# Test_Schematic_V3.net
KiCad netlist of a schematic drawn in EAGLE
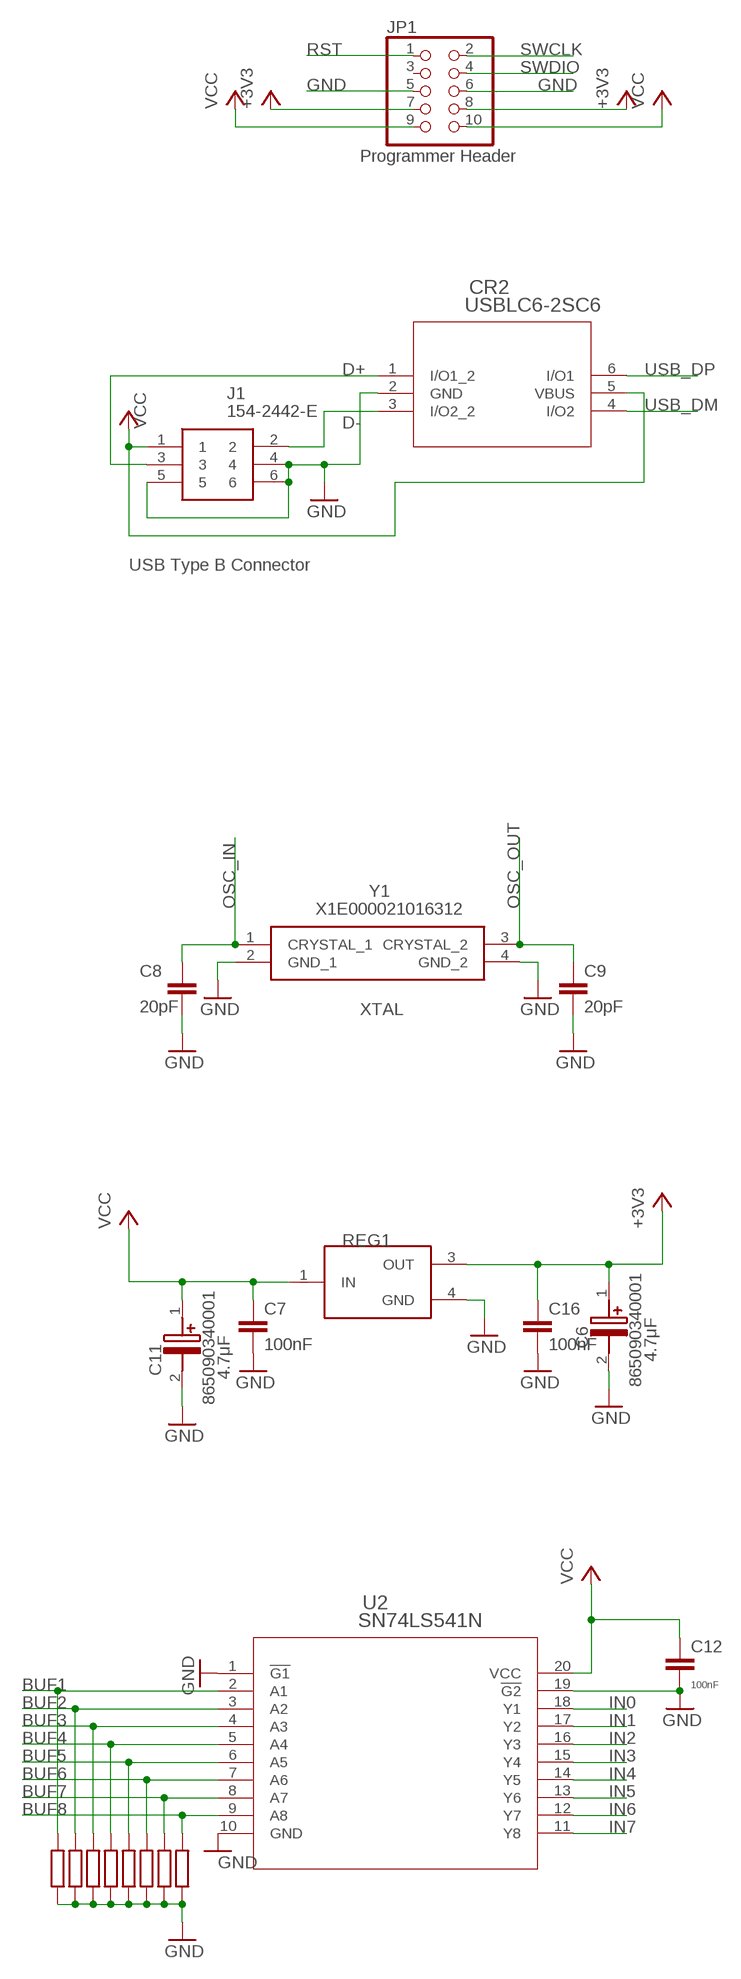
[diagram p0: schematic, sheet 1, part 1 of 2]
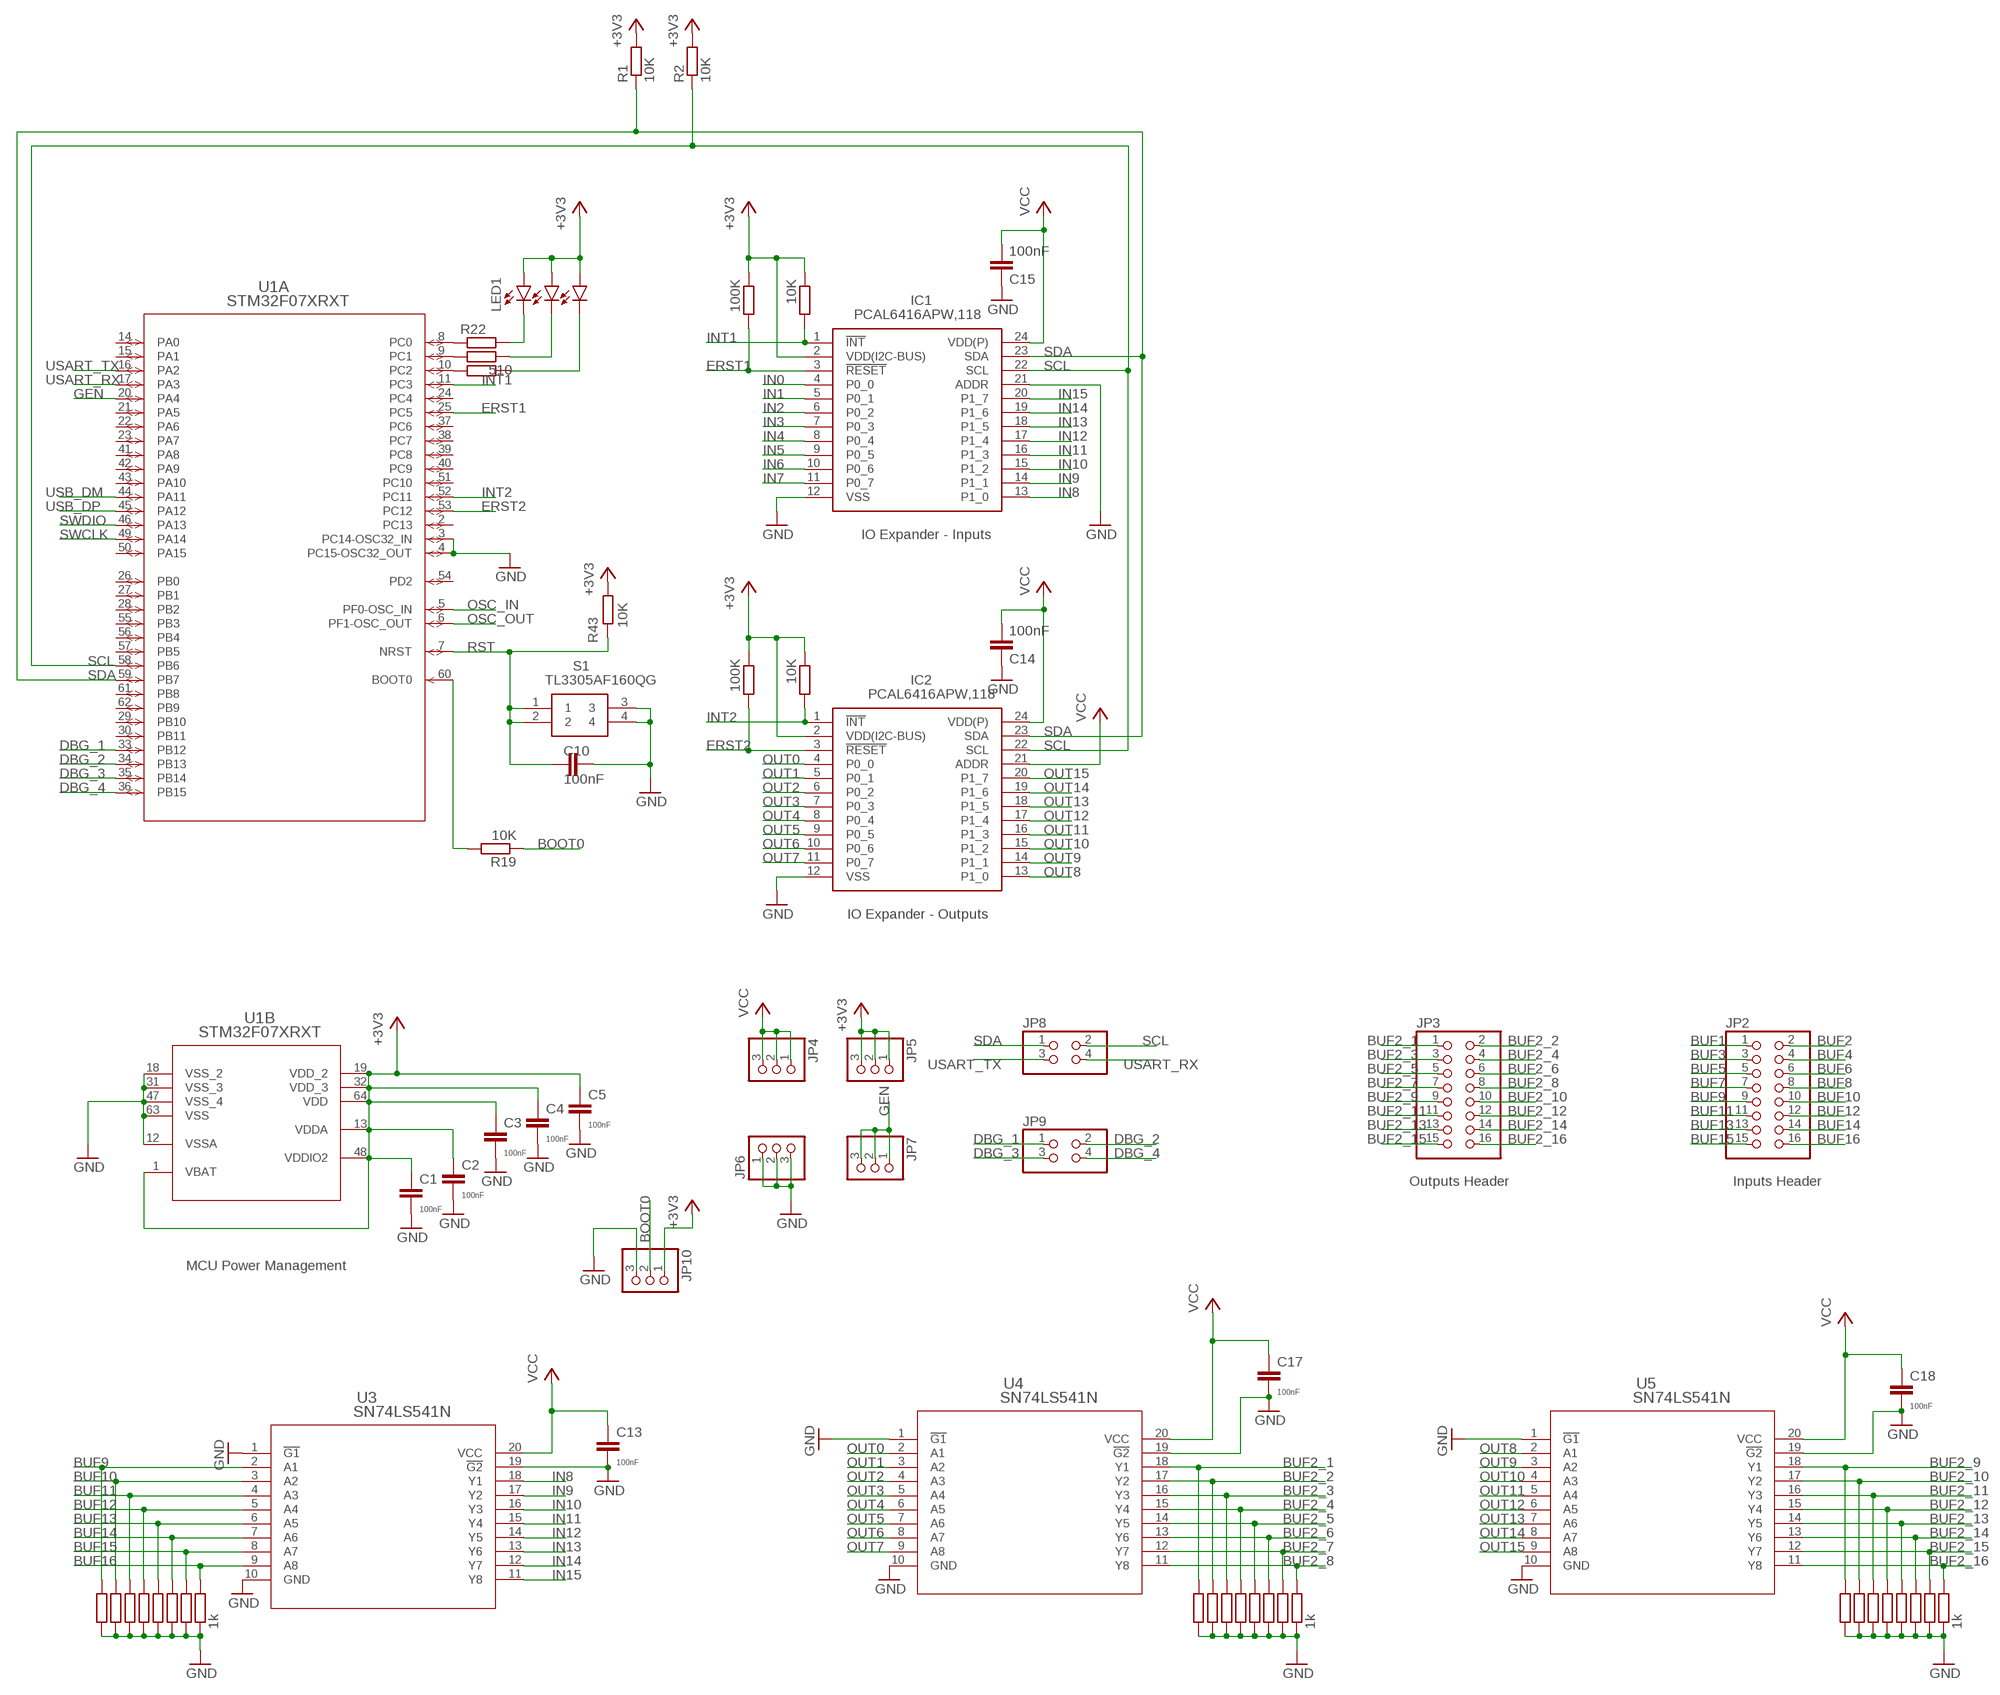
[diagram p1: schematic, sheet 1, part 2 of 2]

(export (version "E")
  (design (tool "Eeschema 10.0.6"))
  (components
    (comp (ref "C1")
      (value "100nF")
      (footprint "eagle-import:C1206")
      (libsource (lib "eagle-import") (part "C-EUC1206"))
    )
    (comp (ref "C2")
      (value "100nF")
      (footprint "eagle-import:C1206")
      (libsource (lib "eagle-import") (part "C-EUC1206"))
    )
    (comp (ref "C3")
      (value "100nF")
      (footprint "eagle-import:C1206")
      (libsource (lib "eagle-import") (part "C-EUC1206"))
    )
    (comp (ref "C4")
      (value "100nF")
      (footprint "eagle-import:C1206")
      (libsource (lib "eagle-import") (part "C-EUC1206"))
    )
    (comp (ref "C5")
      (value "100nF")
      (footprint "eagle-import:C1206")
      (libsource (lib "eagle-import") (part "C-EUC1206"))
    )
    (comp (ref "C6")
      (value "865090340001")
      (footprint "eagle-import:CAPAE430X550N")
      (fields
        (field (name "MOUSER_PART_NUMBER") "710-865090340001")
        (field (name "RS_PART_NUMBER") "8387942P")
        (field (name "CAPACITANCE") "4.7μF")
      )
      (libsource (lib "eagle-import") (part "865090340001"))
    )
    (comp (ref "C7")
      (value "100nF")
      (footprint "eagle-import:C1206")
      (libsource (lib "eagle-import") (part "C-EUC1206"))
    )
    (comp (ref "C8")
      (value "20pF")
      (footprint "eagle-import:C0805K")
      (libsource (lib "eagle-import") (part "C-EUC0805K"))
    )
    (comp (ref "C9")
      (value "20pF")
      (footprint "eagle-import:C0805K")
      (libsource (lib "eagle-import") (part "C-EUC0805K"))
    )
    (comp (ref "C10")
      (value "100nF")
      (footprint "eagle-import:C1206")
      (libsource (lib "eagle-import") (part "C-EUC1206"))
    )
    (comp (ref "C11")
      (value "865090340001")
      (footprint "eagle-import:CAPAE430X550N")
      (fields
        (field (name "MOUSER_PART_NUMBER") "710-865090340001")
        (field (name "RS_PART_NUMBER") "8387942P")
        (field (name "CAPACITANCE") "4.7μF")
      )
      (libsource (lib "eagle-import") (part "865090340001"))
    )
    (comp (ref "C12")
      (value "100nF")
      (footprint "eagle-import:C1206")
      (libsource (lib "eagle-import") (part "C-EUC1206"))
    )
    (comp (ref "C13")
      (value "100nF")
      (footprint "eagle-import:C1206")
      (libsource (lib "eagle-import") (part "C-EUC1206"))
    )
    (comp (ref "C14")
      (value "100nF")
      (footprint "eagle-import:C1206")
      (libsource (lib "eagle-import") (part "C-EUC1206"))
    )
    (comp (ref "C15")
      (value "100nF")
      (footprint "eagle-import:C1206")
      (libsource (lib "eagle-import") (part "C-EUC1206"))
    )
    (comp (ref "C16")
      (value "100nF")
      (footprint "eagle-import:C1206")
      (libsource (lib "eagle-import") (part "C-EUC1206"))
    )
    (comp (ref "C17")
      (value "100nF")
      (footprint "eagle-import:C1206")
      (libsource (lib "eagle-import") (part "C-EUC1206"))
    )
    (comp (ref "C18")
      (value "100nF")
      (footprint "eagle-import:C1206")
      (libsource (lib "eagle-import") (part "C-EUC1206"))
    )
    (comp (ref "CR2")
      (value "USBLC6-2SC6")
      (footprint "eagle-import:SOT23-6L")
      (fields (field (name "MANUFACTURER_PART_NUMBER") "USBLC62SC6"))
      (libsource (lib "eagle-import") (part "USBLC6-2SC6"))
    )
    (comp (ref "IC1")
      (value "PCAL6416APW,118")
      (footprint "eagle-import:SOP65P640X110-24N")
      (fields
        (field (name "MOUSER_PART_NUMBER") "771-PCAL6416APW118")
        (field (name "CUSTOM_DESCRIPTION") "IO Expander - Inputs")
      )
      (libsource (lib "eagle-import") (part "PCAL6416APW,118"))
    )
    (comp (ref "IC2")
      (value "PCAL6416APW,118")
      (footprint "eagle-import:SOP65P640X110-24N")
      (fields
        (field (name "MOUSER_PART_NUMBER") "771-PCAL6416APW118")
        (field (name "CUSTOM_DESCRIPTION") "IO Expander - Outputs")
      )
      (libsource (lib "eagle-import") (part "PCAL6416APW,118"))
    )
    (comp (ref "J1")
      (value "154-2442-E")
      (footprint "eagle-import:1542442E")
      (fields (field (name "CUSTOM_DESCRIPTION") "USB Type B Connector"))
      (libsource (lib "eagle-import") (part "154-2442-E"))
    )
    (comp (ref "JP1")
      (value "PINHD-2X5")
      (footprint "eagle-import:2X05")
      (fields (field (name "HEADER") "Programmer Header"))
      (libsource (lib "eagle-import") (part "PINHD-2X5"))
    )
    (comp (ref "JP2")
      (value "PINHD-2X8")
      (footprint "eagle-import:2X08")
      (fields (field (name "CUSTOM_DESCRIPTION") "Inputs Header"))
      (libsource (lib "eagle-import") (part "PINHD-2X8"))
    )
    (comp (ref "JP3")
      (value "PINHD-2X8")
      (footprint "eagle-import:2X08")
      (fields (field (name "CUSTOM_DESCRIPTION") "Outputs Header"))
      (libsource (lib "eagle-import") (part "PINHD-2X8"))
    )
    (comp (ref "JP4")
      (value "PINHD-1X3")
      (footprint "eagle-import:1X03")
      (libsource (lib "eagle-import") (part "PINHD-1X3"))
    )
    (comp (ref "JP5")
      (value "PINHD-1X3")
      (footprint "eagle-import:1X03")
      (libsource (lib "eagle-import") (part "PINHD-1X3"))
    )
    (comp (ref "JP6")
      (value "PINHD-1X3")
      (footprint "eagle-import:1X03")
      (libsource (lib "eagle-import") (part "PINHD-1X3"))
    )
    (comp (ref "JP7")
      (value "PINHD-1X3")
      (footprint "eagle-import:1X03")
      (libsource (lib "eagle-import") (part "PINHD-1X3"))
    )
    (comp (ref "JP8")
      (value "PINHD-2X2")
      (footprint "eagle-import:2X02")
      (libsource (lib "eagle-import") (part "PINHD-2X2"))
    )
    (comp (ref "JP9")
      (value "PINHD-2X2")
      (footprint "eagle-import:2X02")
      (libsource (lib "eagle-import") (part "PINHD-2X2"))
    )
    (comp (ref "JP10")
      (value "PINHD-1X3")
      (footprint "eagle-import:1X03")
      (libsource (lib "eagle-import") (part "PINHD-1X3"))
    )
    (comp (ref "LED1")
      (value "LEDCHIP-LED0805")
      (footprint "eagle-import:CHIP-LED0805")
      (libsource (lib "eagle-import") (part "LEDCHIP-LED0805"))
    )
    (comp (ref "LED2")
      (value "LEDCHIP-LED0805")
      (footprint "eagle-import:CHIP-LED0805")
      (libsource (lib "eagle-import") (part "LEDCHIP-LED0805"))
    )
    (comp (ref "LED3")
      (value "LEDCHIP-LED0805")
      (footprint "eagle-import:CHIP-LED0805")
      (libsource (lib "eagle-import") (part "LEDCHIP-LED0805"))
    )
    (comp (ref "R1")
      (value "10K")
      (footprint "eagle-import:R2010")
      (libsource (lib "eagle-import") (part "R-EU_R2010"))
    )
    (comp (ref "R2")
      (value "10K")
      (footprint "eagle-import:R2010")
      (libsource (lib "eagle-import") (part "R-EU_R2010"))
    )
    (comp (ref "R11")
      (value "R-EU_R0805")
      (footprint "eagle-import:R0805")
      (libsource (lib "eagle-import") (part "R-EU_R0805"))
    )
    (comp (ref "R12")
      (value "R-EU_R0805")
      (footprint "eagle-import:R0805")
      (libsource (lib "eagle-import") (part "R-EU_R0805"))
    )
    (comp (ref "R13")
      (value "R-EU_R0805")
      (footprint "eagle-import:R0805")
      (libsource (lib "eagle-import") (part "R-EU_R0805"))
    )
    (comp (ref "R14")
      (value "R-EU_R0805")
      (footprint "eagle-import:R0805")
      (libsource (lib "eagle-import") (part "R-EU_R0805"))
    )
    (comp (ref "R15")
      (value "R-EU_R0805")
      (footprint "eagle-import:R0805")
      (libsource (lib "eagle-import") (part "R-EU_R0805"))
    )
    (comp (ref "R16")
      (value "R-EU_R0805")
      (footprint "eagle-import:R0805")
      (libsource (lib "eagle-import") (part "R-EU_R0805"))
    )
    (comp (ref "R17")
      (value "R-EU_R0805")
      (footprint "eagle-import:R0805")
      (libsource (lib "eagle-import") (part "R-EU_R0805"))
    )
    (comp (ref "R18")
      (value "1k")
      (footprint "eagle-import:R0805")
      (libsource (lib "eagle-import") (part "R-EU_R0805"))
    )
    (comp (ref "R19")
      (value "10K")
      (footprint "eagle-import:R2010")
      (libsource (lib "eagle-import") (part "R-EU_R2010"))
    )
    (comp (ref "R20")
      (value "100K")
      (footprint "eagle-import:R2010")
      (libsource (lib "eagle-import") (part "R-EU_R2010"))
    )
    (comp (ref "R21")
      (value "100K")
      (footprint "eagle-import:R2010")
      (libsource (lib "eagle-import") (part "R-EU_R2010"))
    )
    (comp (ref "R22")
      (value "R-EU_R0805")
      (footprint "eagle-import:R0805")
      (libsource (lib "eagle-import") (part "R-EU_R0805"))
    )
    (comp (ref "R23")
      (value "R-EU_R0805")
      (footprint "eagle-import:R0805")
      (libsource (lib "eagle-import") (part "R-EU_R0805"))
    )
    (comp (ref "R24")
      (value "510")
      (footprint "eagle-import:R0805")
      (libsource (lib "eagle-import") (part "R-EU_R0805"))
    )
    (comp (ref "R25")
      (value "10K")
      (footprint "eagle-import:R2010")
      (libsource (lib "eagle-import") (part "R-EU_R2010"))
    )
    (comp (ref "R26")
      (value "10K")
      (footprint "eagle-import:R2010")
      (libsource (lib "eagle-import") (part "R-EU_R2010"))
    )
    (comp (ref "R27")
      (value "1k")
      (footprint "eagle-import:R0805")
      (libsource (lib "eagle-import") (part "R-EU_R0805"))
    )
    (comp (ref "R28")
      (value "R-EU_R0805")
      (footprint "eagle-import:R0805")
      (libsource (lib "eagle-import") (part "R-EU_R0805"))
    )
    (comp (ref "R29")
      (value "R-EU_R0805")
      (footprint "eagle-import:R0805")
      (libsource (lib "eagle-import") (part "R-EU_R0805"))
    )
    (comp (ref "R30")
      (value "R-EU_R0805")
      (footprint "eagle-import:R0805")
      (libsource (lib "eagle-import") (part "R-EU_R0805"))
    )
    (comp (ref "R31")
      (value "R-EU_R0805")
      (footprint "eagle-import:R0805")
      (libsource (lib "eagle-import") (part "R-EU_R0805"))
    )
    (comp (ref "R32")
      (value "R-EU_R0805")
      (footprint "eagle-import:R0805")
      (libsource (lib "eagle-import") (part "R-EU_R0805"))
    )
    (comp (ref "R33")
      (value "R-EU_R0805")
      (footprint "eagle-import:R0805")
      (libsource (lib "eagle-import") (part "R-EU_R0805"))
    )
    (comp (ref "R34")
      (value "R-EU_R0805")
      (footprint "eagle-import:R0805")
      (libsource (lib "eagle-import") (part "R-EU_R0805"))
    )
    (comp (ref "R43")
      (value "10K")
      (footprint "eagle-import:R0805")
      (libsource (lib "eagle-import") (part "R-EU_R0805"))
    )
    (comp (ref "R44")
      (value "1k")
      (footprint "eagle-import:R0805")
      (libsource (lib "eagle-import") (part "R-EU_R0805"))
    )
    (comp (ref "R45")
      (value "R-EU_R0805")
      (footprint "eagle-import:R0805")
      (libsource (lib "eagle-import") (part "R-EU_R0805"))
    )
    (comp (ref "R46")
      (value "R-EU_R0805")
      (footprint "eagle-import:R0805")
      (libsource (lib "eagle-import") (part "R-EU_R0805"))
    )
    (comp (ref "R47")
      (value "R-EU_R0805")
      (footprint "eagle-import:R0805")
      (libsource (lib "eagle-import") (part "R-EU_R0805"))
    )
    (comp (ref "R48")
      (value "R-EU_R0805")
      (footprint "eagle-import:R0805")
      (libsource (lib "eagle-import") (part "R-EU_R0805"))
    )
    (comp (ref "R49")
      (value "R-EU_R0805")
      (footprint "eagle-import:R0805")
      (libsource (lib "eagle-import") (part "R-EU_R0805"))
    )
    (comp (ref "R50")
      (value "R-EU_R0805")
      (footprint "eagle-import:R0805")
      (libsource (lib "eagle-import") (part "R-EU_R0805"))
    )
    (comp (ref "R51")
      (value "R-EU_R0805")
      (footprint "eagle-import:R0805")
      (libsource (lib "eagle-import") (part "R-EU_R0805"))
    )
    (comp (ref "R52")
      (value "1k")
      (footprint "eagle-import:R0805")
      (libsource (lib "eagle-import") (part "R-EU_R0805"))
    )
    (comp (ref "R53")
      (value "R-EU_R0805")
      (footprint "eagle-import:R0805")
      (libsource (lib "eagle-import") (part "R-EU_R0805"))
    )
    (comp (ref "R54")
      (value "R-EU_R0805")
      (footprint "eagle-import:R0805")
      (libsource (lib "eagle-import") (part "R-EU_R0805"))
    )
    (comp (ref "R55")
      (value "R-EU_R0805")
      (footprint "eagle-import:R0805")
      (libsource (lib "eagle-import") (part "R-EU_R0805"))
    )
    (comp (ref "R56")
      (value "R-EU_R0805")
      (footprint "eagle-import:R0805")
      (libsource (lib "eagle-import") (part "R-EU_R0805"))
    )
    (comp (ref "R57")
      (value "R-EU_R0805")
      (footprint "eagle-import:R0805")
      (libsource (lib "eagle-import") (part "R-EU_R0805"))
    )
    (comp (ref "R58")
      (value "R-EU_R0805")
      (footprint "eagle-import:R0805")
      (libsource (lib "eagle-import") (part "R-EU_R0805"))
    )
    (comp (ref "R59")
      (value "R-EU_R0805")
      (footprint "eagle-import:R0805")
      (libsource (lib "eagle-import") (part "R-EU_R0805"))
    )
    (comp (ref "REG1")
      (value "LF33ABDT")
      (footprint "eagle-import:DPAK")
      (libsource (lib "eagle-import") (part "LF33ABDT"))
    )
    (comp (ref "S1")
      (value "TL3305AF160QG")
      (footprint "eagle-import:TL3305AF160QG")
      (fields (field (name "MOUSER_PART_NUMBER") "612-TL3305AF160QG"))
      (libsource (lib "eagle-import") (part "TL3305AF160QG"))
    )
    (comp (ref "U1")
      (value "STM32F07XRXT")
      (footprint "eagle-import:LQFP64-10X10MM")
      (fields (field (name "CUSTOM_DESCRIPTION") "MCU Power Management"))
      (libsource (lib "eagle-import") (part "STM32F07XRXT"))
    )
    (comp (ref "U2")
      (value "SN74LS541N")
      (footprint "eagle-import:N20")
      (libsource (lib "eagle-import") (part "SN74LS541N"))
    )
    (comp (ref "U3")
      (value "SN74LS541N")
      (footprint "eagle-import:N20")
      (libsource (lib "eagle-import") (part "SN74LS541N"))
    )
    (comp (ref "U4")
      (value "SN74LS541N")
      (footprint "eagle-import:N20")
      (libsource (lib "eagle-import") (part "SN74LS541N"))
    )
    (comp (ref "U5")
      (value "SN74LS541N")
      (footprint "eagle-import:N20")
      (libsource (lib "eagle-import") (part "SN74LS541N"))
    )
    (comp (ref "Y1")
      (value "X1E000021016312")
      (footprint "eagle-import:TSX-3225_2")
      (fields (field (name "RS_PART_NUMBER") "9047556P") (field (name "CUSTOM_DESCRIPTION") "XTAL"))
      (libsource (lib "eagle-import") (part "X1E000021016312"))
    )
  )
  (nets
    (net (code "1") (name "+3V3") (class "Default")
      (node (ref "C1") (pin "1") (pinfunction "1_1") (pintype "passive"))
      (node (ref "C16") (pin "1") (pinfunction "1_1") (pintype "passive"))
      (node (ref "C2") (pin "1") (pinfunction "1_1") (pintype "passive"))
      (node (ref "C3") (pin "1") (pinfunction "1_1") (pintype "passive"))
      (node (ref "C4") (pin "1") (pinfunction "1_1") (pintype "passive"))
      (node (ref "C5") (pin "1") (pinfunction "1_1") (pintype "passive"))
      (node (ref "C6") (pin "1") (pinfunction "+_1") (pintype "bidirectional"))
      (node (ref "IC1") (pin "2") (pinfunction "VDD(I2C-BUS)_2") (pintype "bidirectional"))
      (node (ref "IC2") (pin "2") (pinfunction "VDD(I2C-BUS)_2") (pintype "bidirectional"))
      (node (ref "JP1") (pin "7") (pinfunction "7_7") (pintype "passive"))
      (node (ref "JP1") (pin "8") (pinfunction "8_8") (pintype "passive"))
      (node (ref "JP10") (pin "1") (pinfunction "1_1") (pintype "passive"))
      (node (ref "JP5") (pin "1") (pinfunction "1_1") (pintype "passive"))
      (node (ref "JP5") (pin "2") (pinfunction "2_2") (pintype "passive"))
      (node (ref "JP5") (pin "3") (pinfunction "3_3") (pintype "passive"))
      (node (ref "LED1") (pin "A") (pinfunction "A_A") (pintype "passive"))
      (node (ref "LED2") (pin "A") (pinfunction "A_A") (pintype "passive"))
      (node (ref "LED3") (pin "A") (pinfunction "A_A") (pintype "passive"))
      (node (ref "R1") (pin "2") (pinfunction "2_2") (pintype "passive"))
      (node (ref "R2") (pin "2") (pinfunction "2_2") (pintype "passive"))
      (node (ref "R20") (pin "1") (pinfunction "1_1") (pintype "passive"))
      (node (ref "R21") (pin "1") (pinfunction "1_1") (pintype "passive"))
      (node (ref "R25") (pin "1") (pinfunction "1_1") (pintype "passive"))
      (node (ref "R26") (pin "1") (pinfunction "1_1") (pintype "passive"))
      (node (ref "R43") (pin "1") (pinfunction "1_1") (pintype "passive"))
      (node (ref "REG1") (pin "3") (pinfunction "OUT_3") (pintype "power_in"))
      (node (ref "U1") (pin "1") (pinfunction "VBAT_1") (pintype "power_in"))
      (node (ref "U1") (pin "13") (pinfunction "VDDA_13") (pintype "power_in"))
      (node (ref "U1") (pin "19") (pinfunction "VDD_2_19") (pintype "power_in"))
      (node (ref "U1") (pin "32") (pinfunction "VDD_3_32") (pintype "power_in"))
      (node (ref "U1") (pin "48") (pinfunction "VDDIO2_48") (pintype "power_in"))
      (node (ref "U1") (pin "64") (pinfunction "VDD_64") (pintype "power_in"))
    )
    (net (code "2") (name "/BOOT0") (class "Default")
      (node (ref "JP10") (pin "2") (pinfunction "2_2") (pintype "passive"))
      (node (ref "R19") (pin "1") (pinfunction "1_1") (pintype "passive"))
    )
    (net (code "3") (name "/BUF1") (class "Default")
      (node (ref "JP2") (pin "1") (pinfunction "1_1") (pintype "passive"))
      (node (ref "R11") (pin "2") (pinfunction "2_2") (pintype "passive"))
      (node (ref "U2") (pin "2") (pinfunction "A1_2") (pintype "input"))
    )
    (net (code "4") (name "/BUF2") (class "Default")
      (node (ref "JP2") (pin "2") (pinfunction "2_2") (pintype "passive"))
      (node (ref "R12") (pin "2") (pinfunction "2_2") (pintype "passive"))
      (node (ref "U2") (pin "3") (pinfunction "A2_3") (pintype "input"))
    )
    (net (code "5") (name "/BUF2_1") (class "Default")
      (node (ref "JP3") (pin "1") (pinfunction "1_1") (pintype "passive"))
      (node (ref "R51") (pin "2") (pinfunction "2_2") (pintype "passive"))
      (node (ref "U4") (pin "18") (pinfunction "Y1_18") (pintype "output"))
    )
    (net (code "6") (name "/BUF2_2") (class "Default")
      (node (ref "JP3") (pin "2") (pinfunction "2_2") (pintype "passive"))
      (node (ref "R50") (pin "2") (pinfunction "2_2") (pintype "passive"))
      (node (ref "U4") (pin "17") (pinfunction "Y2_17") (pintype "output"))
    )
    (net (code "7") (name "/BUF2_3") (class "Default")
      (node (ref "JP3") (pin "3") (pinfunction "3_3") (pintype "passive"))
      (node (ref "R49") (pin "2") (pinfunction "2_2") (pintype "passive"))
      (node (ref "U4") (pin "16") (pinfunction "Y3_16") (pintype "output"))
    )
    (net (code "8") (name "/BUF2_4") (class "Default")
      (node (ref "JP3") (pin "4") (pinfunction "4_4") (pintype "passive"))
      (node (ref "R48") (pin "2") (pinfunction "2_2") (pintype "passive"))
      (node (ref "U4") (pin "15") (pinfunction "Y4_15") (pintype "output"))
    )
    (net (code "9") (name "/BUF2_5") (class "Default")
      (node (ref "JP3") (pin "5") (pinfunction "5_5") (pintype "passive"))
      (node (ref "R47") (pin "2") (pinfunction "2_2") (pintype "passive"))
      (node (ref "U4") (pin "14") (pinfunction "Y5_14") (pintype "output"))
    )
    (net (code "10") (name "/BUF2_6") (class "Default")
      (node (ref "JP3") (pin "6") (pinfunction "6_6") (pintype "passive"))
      (node (ref "R46") (pin "1") (pinfunction "1_1") (pintype "passive"))
      (node (ref "U4") (pin "13") (pinfunction "Y6_13") (pintype "output"))
    )
    (net (code "11") (name "/BUF2_7") (class "Default")
      (node (ref "JP3") (pin "7") (pinfunction "7_7") (pintype "passive"))
      (node (ref "R45") (pin "2") (pinfunction "2_2") (pintype "passive"))
      (node (ref "U4") (pin "12") (pinfunction "Y7_12") (pintype "output"))
    )
    (net (code "12") (name "/BUF2_8") (class "Default")
      (node (ref "JP3") (pin "8") (pinfunction "8_8") (pintype "passive"))
      (node (ref "R44") (pin "2") (pinfunction "2_2") (pintype "passive"))
      (node (ref "U4") (pin "11") (pinfunction "Y8_11") (pintype "output"))
    )
    (net (code "13") (name "/BUF2_9") (class "Default")
      (node (ref "JP3") (pin "9") (pinfunction "9_9") (pintype "passive"))
      (node (ref "R59") (pin "2") (pinfunction "2_2") (pintype "passive"))
      (node (ref "U5") (pin "18") (pinfunction "Y1_18") (pintype "output"))
    )
    (net (code "14") (name "/BUF2_10") (class "Default")
      (node (ref "JP3") (pin "10") (pinfunction "10_10") (pintype "passive"))
      (node (ref "R58") (pin "2") (pinfunction "2_2") (pintype "passive"))
      (node (ref "U5") (pin "17") (pinfunction "Y2_17") (pintype "output"))
    )
    (net (code "15") (name "/BUF2_11") (class "Default")
      (node (ref "JP3") (pin "11") (pinfunction "11_11") (pintype "passive"))
      (node (ref "R57") (pin "2") (pinfunction "2_2") (pintype "passive"))
      (node (ref "U5") (pin "16") (pinfunction "Y3_16") (pintype "output"))
    )
    (net (code "16") (name "/BUF2_12") (class "Default")
      (node (ref "JP3") (pin "12") (pinfunction "12_12") (pintype "passive"))
      (node (ref "R56") (pin "2") (pinfunction "2_2") (pintype "passive"))
      (node (ref "U5") (pin "15") (pinfunction "Y4_15") (pintype "output"))
    )
    (net (code "17") (name "/BUF2_13") (class "Default")
      (node (ref "JP3") (pin "13") (pinfunction "13_13") (pintype "passive"))
      (node (ref "R55") (pin "2") (pinfunction "2_2") (pintype "passive"))
      (node (ref "U5") (pin "14") (pinfunction "Y5_14") (pintype "output"))
    )
    (net (code "18") (name "/BUF2_14") (class "Default")
      (node (ref "JP3") (pin "14") (pinfunction "14_14") (pintype "passive"))
      (node (ref "R54") (pin "1") (pinfunction "1_1") (pintype "passive"))
      (node (ref "U5") (pin "13") (pinfunction "Y6_13") (pintype "output"))
    )
    (net (code "19") (name "/BUF2_15") (class "Default")
      (node (ref "JP3") (pin "15") (pinfunction "15_15") (pintype "passive"))
      (node (ref "R53") (pin "2") (pinfunction "2_2") (pintype "passive"))
      (node (ref "U5") (pin "12") (pinfunction "Y7_12") (pintype "output"))
    )
    (net (code "20") (name "/BUF2_16") (class "Default")
      (node (ref "JP3") (pin "16") (pinfunction "16_16") (pintype "passive"))
      (node (ref "R52") (pin "2") (pinfunction "2_2") (pintype "passive"))
      (node (ref "U5") (pin "11") (pinfunction "Y8_11") (pintype "output"))
    )
    (net (code "21") (name "/BUF3") (class "Default")
      (node (ref "JP2") (pin "3") (pinfunction "3_3") (pintype "passive"))
      (node (ref "R13") (pin "2") (pinfunction "2_2") (pintype "passive"))
      (node (ref "U2") (pin "4") (pinfunction "A3_4") (pintype "input"))
    )
    (net (code "22") (name "/BUF4") (class "Default")
      (node (ref "JP2") (pin "4") (pinfunction "4_4") (pintype "passive"))
      (node (ref "R14") (pin "2") (pinfunction "2_2") (pintype "passive"))
      (node (ref "U2") (pin "5") (pinfunction "A4_5") (pintype "input"))
    )
    (net (code "23") (name "/BUF5") (class "Default")
      (node (ref "JP2") (pin "5") (pinfunction "5_5") (pintype "passive"))
      (node (ref "R15") (pin "2") (pinfunction "2_2") (pintype "passive"))
      (node (ref "U2") (pin "6") (pinfunction "A5_6") (pintype "input"))
    )
    (net (code "24") (name "/BUF6") (class "Default")
      (node (ref "JP2") (pin "6") (pinfunction "6_6") (pintype "passive"))
      (node (ref "R16") (pin "2") (pinfunction "2_2") (pintype "passive"))
      (node (ref "U2") (pin "7") (pinfunction "A6_7") (pintype "input"))
    )
    (net (code "25") (name "/BUF7") (class "Default")
      (node (ref "JP2") (pin "7") (pinfunction "7_7") (pintype "passive"))
      (node (ref "R17") (pin "2") (pinfunction "2_2") (pintype "passive"))
      (node (ref "U2") (pin "8") (pinfunction "A7_8") (pintype "input"))
    )
    (net (code "26") (name "/BUF8") (class "Default")
      (node (ref "JP2") (pin "8") (pinfunction "8_8") (pintype "passive"))
      (node (ref "R18") (pin "2") (pinfunction "2_2") (pintype "passive"))
      (node (ref "U2") (pin "9") (pinfunction "A8_9") (pintype "input"))
    )
    (net (code "27") (name "/BUF9") (class "Default")
      (node (ref "JP2") (pin "9") (pinfunction "9_9") (pintype "passive"))
      (node (ref "R34") (pin "2") (pinfunction "2_2") (pintype "passive"))
      (node (ref "U3") (pin "2") (pinfunction "A1_2") (pintype "input"))
    )
    (net (code "28") (name "/BUF10") (class "Default")
      (node (ref "JP2") (pin "10") (pinfunction "10_10") (pintype "passive"))
      (node (ref "R33") (pin "2") (pinfunction "2_2") (pintype "passive"))
      (node (ref "U3") (pin "3") (pinfunction "A2_3") (pintype "input"))
    )
    (net (code "29") (name "/BUF11") (class "Default")
      (node (ref "JP2") (pin "11") (pinfunction "11_11") (pintype "passive"))
      (node (ref "R32") (pin "2") (pinfunction "2_2") (pintype "passive"))
      (node (ref "U3") (pin "4") (pinfunction "A3_4") (pintype "input"))
    )
    (net (code "30") (name "/BUF12") (class "Default")
      (node (ref "JP2") (pin "12") (pinfunction "12_12") (pintype "passive"))
      (node (ref "R31") (pin "2") (pinfunction "2_2") (pintype "passive"))
      (node (ref "U3") (pin "5") (pinfunction "A4_5") (pintype "input"))
    )
    (net (code "31") (name "/BUF13") (class "Default")
      (node (ref "JP2") (pin "13") (pinfunction "13_13") (pintype "passive"))
      (node (ref "R30") (pin "2") (pinfunction "2_2") (pintype "passive"))
      (node (ref "U3") (pin "6") (pinfunction "A5_6") (pintype "input"))
    )
    (net (code "32") (name "/BUF14") (class "Default")
      (node (ref "JP2") (pin "14") (pinfunction "14_14") (pintype "passive"))
      (node (ref "R29") (pin "1") (pinfunction "1_1") (pintype "passive"))
      (node (ref "U3") (pin "7") (pinfunction "A6_7") (pintype "input"))
    )
    (net (code "33") (name "/BUF15") (class "Default")
      (node (ref "JP2") (pin "15") (pinfunction "15_15") (pintype "passive"))
      (node (ref "R28") (pin "2") (pinfunction "2_2") (pintype "passive"))
      (node (ref "U3") (pin "8") (pinfunction "A7_8") (pintype "input"))
    )
    (net (code "34") (name "/BUF16") (class "Default")
      (node (ref "JP2") (pin "16") (pinfunction "16_16") (pintype "passive"))
      (node (ref "R27") (pin "2") (pinfunction "2_2") (pintype "passive"))
      (node (ref "U3") (pin "9") (pinfunction "A8_9") (pintype "input"))
    )
    (net (code "35") (name "/D+") (class "Default")
      (node (ref "CR2") (pin "1") (pinfunction "I/O1_2_1") (pintype "bidirectional"))
      (node (ref "J1") (pin "3") (pinfunction "3_3") (pintype "bidirectional"))
    )
    (net (code "36") (name "/D-") (class "Default")
      (node (ref "CR2") (pin "3") (pinfunction "I/O2_2_3") (pintype "bidirectional"))
      (node (ref "J1") (pin "2") (pinfunction "2_2") (pintype "bidirectional"))
    )
    (net (code "37") (name "/DBG_1") (class "Default")
      (node (ref "JP9") (pin "1") (pinfunction "1_1") (pintype "passive"))
      (node (ref "U1") (pin "33") (pinfunction "PB12_33") (pintype "bidirectional"))
    )
    (net (code "38") (name "/DBG_2") (class "Default")
      (node (ref "JP9") (pin "2") (pinfunction "2_2") (pintype "passive"))
      (node (ref "U1") (pin "34") (pinfunction "PB13_34") (pintype "bidirectional"))
    )
    (net (code "39") (name "/DBG_3") (class "Default")
      (node (ref "JP9") (pin "3") (pinfunction "3_3") (pintype "passive"))
      (node (ref "U1") (pin "35") (pinfunction "PB14_35") (pintype "bidirectional"))
    )
    (net (code "40") (name "/DBG_4") (class "Default")
      (node (ref "JP9") (pin "4") (pinfunction "4_4") (pintype "passive"))
      (node (ref "U1") (pin "36") (pinfunction "PB15_36") (pintype "bidirectional"))
    )
    (net (code "41") (name "/ERST1") (class "Default")
      (node (ref "IC1") (pin "3") (pinfunction "~{RESET}_3") (pintype "bidirectional"))
      (node (ref "R20") (pin "2") (pinfunction "2_2") (pintype "passive"))
      (node (ref "U1") (pin "25") (pinfunction "PC5_25") (pintype "bidirectional"))
    )
    (net (code "42") (name "/ERST2") (class "Default")
      (node (ref "IC2") (pin "3") (pinfunction "~{RESET}_3") (pintype "bidirectional"))
      (node (ref "R21") (pin "2") (pinfunction "2_2") (pintype "passive"))
      (node (ref "U1") (pin "53") (pinfunction "PC12_53") (pintype "bidirectional"))
    )
    (net (code "43") (name "/GEN") (class "Default")
      (node (ref "JP7") (pin "1") (pinfunction "1_1") (pintype "passive"))
      (node (ref "JP7") (pin "2") (pinfunction "2_2") (pintype "passive"))
      (node (ref "JP7") (pin "3") (pinfunction "3_3") (pintype "passive"))
      (node (ref "U1") (pin "20") (pinfunction "PA4_20") (pintype "bidirectional"))
    )
    (net (code "44") (name "/IN0") (class "Default")
      (node (ref "IC1") (pin "4") (pinfunction "P0_0_4") (pintype "bidirectional"))
      (node (ref "U2") (pin "18") (pinfunction "Y1_18") (pintype "output"))
    )
    (net (code "45") (name "/IN1") (class "Default")
      (node (ref "IC1") (pin "5") (pinfunction "P0_1_5") (pintype "bidirectional"))
      (node (ref "U2") (pin "17") (pinfunction "Y2_17") (pintype "output"))
    )
    (net (code "46") (name "/IN2") (class "Default")
      (node (ref "IC1") (pin "6") (pinfunction "P0_2_6") (pintype "bidirectional"))
      (node (ref "U2") (pin "16") (pinfunction "Y3_16") (pintype "output"))
    )
    (net (code "47") (name "/IN3") (class "Default")
      (node (ref "IC1") (pin "7") (pinfunction "P0_3_7") (pintype "bidirectional"))
      (node (ref "U2") (pin "15") (pinfunction "Y4_15") (pintype "output"))
    )
    (net (code "48") (name "/IN4") (class "Default")
      (node (ref "IC1") (pin "8") (pinfunction "P0_4_8") (pintype "bidirectional"))
      (node (ref "U2") (pin "14") (pinfunction "Y5_14") (pintype "output"))
    )
    (net (code "49") (name "/IN5") (class "Default")
      (node (ref "IC1") (pin "9") (pinfunction "P0_5_9") (pintype "bidirectional"))
      (node (ref "U2") (pin "13") (pinfunction "Y6_13") (pintype "output"))
    )
    (net (code "50") (name "/IN6") (class "Default")
      (node (ref "IC1") (pin "10") (pinfunction "P0_6_10") (pintype "bidirectional"))
      (node (ref "U2") (pin "12") (pinfunction "Y7_12") (pintype "output"))
    )
    (net (code "51") (name "/IN7") (class "Default")
      (node (ref "IC1") (pin "11") (pinfunction "P0_7_11") (pintype "bidirectional"))
      (node (ref "U2") (pin "11") (pinfunction "Y8_11") (pintype "output"))
    )
    (net (code "52") (name "/IN8") (class "Default")
      (node (ref "IC1") (pin "13") (pinfunction "P1_0_13") (pintype "bidirectional"))
      (node (ref "U3") (pin "18") (pinfunction "Y1_18") (pintype "output"))
    )
    (net (code "53") (name "/IN9") (class "Default")
      (node (ref "IC1") (pin "14") (pinfunction "P1_1_14") (pintype "bidirectional"))
      (node (ref "U3") (pin "17") (pinfunction "Y2_17") (pintype "output"))
    )
    (net (code "54") (name "/IN10") (class "Default")
      (node (ref "IC1") (pin "15") (pinfunction "P1_2_15") (pintype "bidirectional"))
      (node (ref "U3") (pin "16") (pinfunction "Y3_16") (pintype "output"))
    )
    (net (code "55") (name "/IN11") (class "Default")
      (node (ref "IC1") (pin "16") (pinfunction "P1_3_16") (pintype "bidirectional"))
      (node (ref "U3") (pin "15") (pinfunction "Y4_15") (pintype "output"))
    )
    (net (code "56") (name "/IN12") (class "Default")
      (node (ref "IC1") (pin "17") (pinfunction "P1_4_17") (pintype "bidirectional"))
      (node (ref "U3") (pin "14") (pinfunction "Y5_14") (pintype "output"))
    )
    (net (code "57") (name "/IN13") (class "Default")
      (node (ref "IC1") (pin "18") (pinfunction "P1_5_18") (pintype "bidirectional"))
      (node (ref "U3") (pin "13") (pinfunction "Y6_13") (pintype "output"))
    )
    (net (code "58") (name "/IN14") (class "Default")
      (node (ref "IC1") (pin "19") (pinfunction "P1_6_19") (pintype "bidirectional"))
      (node (ref "U3") (pin "12") (pinfunction "Y7_12") (pintype "output"))
    )
    (net (code "59") (name "/IN15") (class "Default")
      (node (ref "IC1") (pin "20") (pinfunction "P1_7_20") (pintype "bidirectional"))
      (node (ref "U3") (pin "11") (pinfunction "Y8_11") (pintype "output"))
    )
    (net (code "60") (name "/INT1") (class "Default")
      (node (ref "IC1") (pin "1") (pinfunction "~{INT}_1") (pintype "bidirectional"))
      (node (ref "R26") (pin "2") (pinfunction "2_2") (pintype "passive"))
      (node (ref "U1") (pin "11") (pinfunction "PC3_11") (pintype "bidirectional"))
    )
    (net (code "61") (name "/INT2") (class "Default")
      (node (ref "IC2") (pin "1") (pinfunction "~{INT}_1") (pintype "bidirectional"))
      (node (ref "R25") (pin "2") (pinfunction "2_2") (pintype "passive"))
      (node (ref "U1") (pin "52") (pinfunction "PC11_52") (pintype "bidirectional"))
    )
    (net (code "62") (name "/OSC_IN") (class "Default")
      (node (ref "C8") (pin "1") (pinfunction "1_1") (pintype "passive"))
      (node (ref "U1") (pin "5") (pinfunction "PF0-OSC_IN_5") (pintype "bidirectional"))
      (node (ref "Y1") (pin "1") (pinfunction "CRYSTAL_1_1") (pintype "bidirectional"))
    )
    (net (code "63") (name "/OSC_OUT") (class "Default")
      (node (ref "C9") (pin "1") (pinfunction "1_1") (pintype "passive"))
      (node (ref "U1") (pin "6") (pinfunction "PF1-OSC_OUT_6") (pintype "bidirectional"))
      (node (ref "Y1") (pin "3") (pinfunction "CRYSTAL_2_3") (pintype "bidirectional"))
    )
    (net (code "64") (name "/OUT0") (class "Default")
      (node (ref "IC2") (pin "4") (pinfunction "P0_0_4") (pintype "bidirectional"))
      (node (ref "U4") (pin "2") (pinfunction "A1_2") (pintype "input"))
    )
    (net (code "65") (name "/OUT1") (class "Default")
      (node (ref "IC2") (pin "5") (pinfunction "P0_1_5") (pintype "bidirectional"))
      (node (ref "U4") (pin "3") (pinfunction "A2_3") (pintype "input"))
    )
    (net (code "66") (name "/OUT2") (class "Default")
      (node (ref "IC2") (pin "6") (pinfunction "P0_2_6") (pintype "bidirectional"))
      (node (ref "U4") (pin "4") (pinfunction "A3_4") (pintype "input"))
    )
    (net (code "67") (name "/OUT3") (class "Default")
      (node (ref "IC2") (pin "7") (pinfunction "P0_3_7") (pintype "bidirectional"))
      (node (ref "U4") (pin "5") (pinfunction "A4_5") (pintype "input"))
    )
    (net (code "68") (name "/OUT4") (class "Default")
      (node (ref "IC2") (pin "8") (pinfunction "P0_4_8") (pintype "bidirectional"))
      (node (ref "U4") (pin "6") (pinfunction "A5_6") (pintype "input"))
    )
    (net (code "69") (name "/OUT5") (class "Default")
      (node (ref "IC2") (pin "9") (pinfunction "P0_5_9") (pintype "bidirectional"))
      (node (ref "U4") (pin "7") (pinfunction "A6_7") (pintype "input"))
    )
    (net (code "70") (name "/OUT6") (class "Default")
      (node (ref "IC2") (pin "10") (pinfunction "P0_6_10") (pintype "bidirectional"))
      (node (ref "U4") (pin "8") (pinfunction "A7_8") (pintype "input"))
    )
    (net (code "71") (name "/OUT7") (class "Default")
      (node (ref "IC2") (pin "11") (pinfunction "P0_7_11") (pintype "bidirectional"))
      (node (ref "U4") (pin "9") (pinfunction "A8_9") (pintype "input"))
    )
    (net (code "72") (name "/OUT8") (class "Default")
      (node (ref "IC2") (pin "13") (pinfunction "P1_0_13") (pintype "bidirectional"))
      (node (ref "U5") (pin "2") (pinfunction "A1_2") (pintype "input"))
    )
    (net (code "73") (name "/OUT9") (class "Default")
      (node (ref "IC2") (pin "14") (pinfunction "P1_1_14") (pintype "bidirectional"))
      (node (ref "U5") (pin "3") (pinfunction "A2_3") (pintype "input"))
    )
    (net (code "74") (name "/OUT10") (class "Default")
      (node (ref "IC2") (pin "15") (pinfunction "P1_2_15") (pintype "bidirectional"))
      (node (ref "U5") (pin "4") (pinfunction "A3_4") (pintype "input"))
    )
    (net (code "75") (name "/OUT11") (class "Default")
      (node (ref "IC2") (pin "16") (pinfunction "P1_3_16") (pintype "bidirectional"))
      (node (ref "U5") (pin "5") (pinfunction "A4_5") (pintype "input"))
    )
    (net (code "76") (name "/OUT12") (class "Default")
      (node (ref "IC2") (pin "17") (pinfunction "P1_4_17") (pintype "bidirectional"))
      (node (ref "U5") (pin "6") (pinfunction "A5_6") (pintype "input"))
    )
    (net (code "77") (name "/OUT13") (class "Default")
      (node (ref "IC2") (pin "18") (pinfunction "P1_5_18") (pintype "bidirectional"))
      (node (ref "U5") (pin "7") (pinfunction "A6_7") (pintype "input"))
    )
    (net (code "78") (name "/OUT14") (class "Default")
      (node (ref "IC2") (pin "19") (pinfunction "P1_6_19") (pintype "bidirectional"))
      (node (ref "U5") (pin "8") (pinfunction "A7_8") (pintype "input"))
    )
    (net (code "79") (name "/OUT15") (class "Default")
      (node (ref "IC2") (pin "20") (pinfunction "P1_7_20") (pintype "bidirectional"))
      (node (ref "U5") (pin "9") (pinfunction "A8_9") (pintype "input"))
    )
    (net (code "80") (name "/RST") (class "Default")
      (node (ref "C10") (pin "1") (pinfunction "1_1") (pintype "passive"))
      (node (ref "JP1") (pin "1") (pinfunction "1_1") (pintype "passive"))
      (node (ref "R43") (pin "2") (pinfunction "2_2") (pintype "passive"))
      (node (ref "S1") (pin "1") (pinfunction "1_1") (pintype "bidirectional"))
      (node (ref "S1") (pin "2") (pinfunction "2_2") (pintype "bidirectional"))
      (node (ref "U1") (pin "7") (pinfunction "NRST_7") (pintype "bidirectional"))
    )
    (net (code "81") (name "/SCL") (class "Default")
      (node (ref "IC1") (pin "22") (pinfunction "SCL_22") (pintype "bidirectional"))
      (node (ref "IC2") (pin "22") (pinfunction "SCL_22") (pintype "bidirectional"))
      (node (ref "JP8") (pin "2") (pinfunction "2_2") (pintype "passive"))
      (node (ref "R2") (pin "1") (pinfunction "1_1") (pintype "passive"))
      (node (ref "U1") (pin "58") (pinfunction "PB6_58") (pintype "bidirectional"))
    )
    (net (code "82") (name "/SDA") (class "Default")
      (node (ref "IC1") (pin "23") (pinfunction "SDA_23") (pintype "bidirectional"))
      (node (ref "IC2") (pin "23") (pinfunction "SDA_23") (pintype "bidirectional"))
      (node (ref "JP8") (pin "1") (pinfunction "1_1") (pintype "passive"))
      (node (ref "R1") (pin "1") (pinfunction "1_1") (pintype "passive"))
      (node (ref "U1") (pin "59") (pinfunction "PB7_59") (pintype "bidirectional"))
    )
    (net (code "83") (name "/SWCLK") (class "Default")
      (node (ref "JP1") (pin "2") (pinfunction "2_2") (pintype "passive"))
      (node (ref "U1") (pin "49") (pinfunction "PA14_49") (pintype "bidirectional"))
    )
    (net (code "84") (name "/SWDIO") (class "Default")
      (node (ref "JP1") (pin "4") (pinfunction "4_4") (pintype "passive"))
      (node (ref "U1") (pin "46") (pinfunction "PA13_46") (pintype "bidirectional"))
    )
    (net (code "85") (name "/USART_RX") (class "Default")
      (node (ref "JP8") (pin "4") (pinfunction "4_4") (pintype "passive"))
      (node (ref "U1") (pin "17") (pinfunction "PA3_17") (pintype "bidirectional"))
    )
    (net (code "86") (name "/USART_TX") (class "Default")
      (node (ref "JP8") (pin "3") (pinfunction "3_3") (pintype "passive"))
      (node (ref "U1") (pin "16") (pinfunction "PA2_16") (pintype "bidirectional"))
    )
    (net (code "87") (name "/USB_DM") (class "Default")
      (node (ref "CR2") (pin "4") (pinfunction "I/O2_4") (pintype "bidirectional"))
      (node (ref "U1") (pin "44") (pinfunction "PA11_44") (pintype "bidirectional"))
    )
    (net (code "88") (name "/USB_DP") (class "Default")
      (node (ref "CR2") (pin "6") (pinfunction "I/O1_6") (pintype "bidirectional"))
      (node (ref "U1") (pin "45") (pinfunction "PA12_45") (pintype "bidirectional"))
    )
    (net (code "89") (name "GND") (class "Default")
      (node (ref "C1") (pin "2") (pinfunction "2_2") (pintype "passive"))
      (node (ref "C10") (pin "2") (pinfunction "2_2") (pintype "passive"))
      (node (ref "C11") (pin "2") (pinfunction "-_2") (pintype "bidirectional"))
      (node (ref "C12") (pin "2") (pinfunction "2_2") (pintype "passive"))
      (node (ref "C13") (pin "2") (pinfunction "2_2") (pintype "passive"))
      (node (ref "C14") (pin "1") (pinfunction "1_1") (pintype "passive"))
      (node (ref "C15") (pin "1") (pinfunction "1_1") (pintype "passive"))
      (node (ref "C16") (pin "2") (pinfunction "2_2") (pintype "passive"))
      (node (ref "C17") (pin "2") (pinfunction "2_2") (pintype "passive"))
      (node (ref "C18") (pin "2") (pinfunction "2_2") (pintype "passive"))
      (node (ref "C2") (pin "2") (pinfunction "2_2") (pintype "passive"))
      (node (ref "C3") (pin "2") (pinfunction "2_2") (pintype "passive"))
      (node (ref "C4") (pin "2") (pinfunction "2_2") (pintype "passive"))
      (node (ref "C5") (pin "2") (pinfunction "2_2") (pintype "passive"))
      (node (ref "C6") (pin "2") (pinfunction "-_2") (pintype "bidirectional"))
      (node (ref "C7") (pin "2") (pinfunction "2_2") (pintype "passive"))
      (node (ref "C8") (pin "2") (pinfunction "2_2") (pintype "passive"))
      (node (ref "C9") (pin "2") (pinfunction "2_2") (pintype "passive"))
      (node (ref "CR2") (pin "2") (pinfunction "GND_2") (pintype "power_in"))
      (node (ref "IC1") (pin "12") (pinfunction "VSS_12") (pintype "bidirectional"))
      (node (ref "IC1") (pin "21") (pinfunction "ADDR_21") (pintype "bidirectional"))
      (node (ref "IC2") (pin "12") (pinfunction "VSS_12") (pintype "bidirectional"))
      (node (ref "J1") (pin "4") (pinfunction "4_4") (pintype "bidirectional"))
      (node (ref "J1") (pin "5") (pinfunction "5_5") (pintype "bidirectional"))
      (node (ref "J1") (pin "6") (pinfunction "6_6") (pintype "bidirectional"))
      (node (ref "JP1") (pin "5") (pinfunction "5_5") (pintype "passive"))
      (node (ref "JP1") (pin "6") (pinfunction "6_6") (pintype "passive"))
      (node (ref "JP10") (pin "3") (pinfunction "3_3") (pintype "passive"))
      (node (ref "JP6") (pin "1") (pinfunction "1_1") (pintype "passive"))
      (node (ref "JP6") (pin "2") (pinfunction "2_2") (pintype "passive"))
      (node (ref "JP6") (pin "3") (pinfunction "3_3") (pintype "passive"))
      (node (ref "R11") (pin "1") (pinfunction "1_1") (pintype "passive"))
      (node (ref "R12") (pin "1") (pinfunction "1_1") (pintype "passive"))
      (node (ref "R13") (pin "1") (pinfunction "1_1") (pintype "passive"))
      (node (ref "R14") (pin "1") (pinfunction "1_1") (pintype "passive"))
      (node (ref "R15") (pin "1") (pinfunction "1_1") (pintype "passive"))
      (node (ref "R16") (pin "1") (pinfunction "1_1") (pintype "passive"))
      (node (ref "R17") (pin "1") (pinfunction "1_1") (pintype "passive"))
      (node (ref "R18") (pin "1") (pinfunction "1_1") (pintype "passive"))
      (node (ref "R27") (pin "1") (pinfunction "1_1") (pintype "passive"))
      (node (ref "R28") (pin "1") (pinfunction "1_1") (pintype "passive"))
      (node (ref "R29") (pin "2") (pinfunction "2_2") (pintype "passive"))
      (node (ref "R30") (pin "1") (pinfunction "1_1") (pintype "passive"))
      (node (ref "R31") (pin "1") (pinfunction "1_1") (pintype "passive"))
      (node (ref "R32") (pin "1") (pinfunction "1_1") (pintype "passive"))
      (node (ref "R33") (pin "1") (pinfunction "1_1") (pintype "passive"))
      (node (ref "R34") (pin "1") (pinfunction "1_1") (pintype "passive"))
      (node (ref "R44") (pin "1") (pinfunction "1_1") (pintype "passive"))
      (node (ref "R45") (pin "1") (pinfunction "1_1") (pintype "passive"))
      (node (ref "R46") (pin "2") (pinfunction "2_2") (pintype "passive"))
      (node (ref "R47") (pin "1") (pinfunction "1_1") (pintype "passive"))
      (node (ref "R48") (pin "1") (pinfunction "1_1") (pintype "passive"))
      (node (ref "R49") (pin "1") (pinfunction "1_1") (pintype "passive"))
      (node (ref "R50") (pin "1") (pinfunction "1_1") (pintype "passive"))
      (node (ref "R51") (pin "1") (pinfunction "1_1") (pintype "passive"))
      (node (ref "R52") (pin "1") (pinfunction "1_1") (pintype "passive"))
      (node (ref "R53") (pin "1") (pinfunction "1_1") (pintype "passive"))
      (node (ref "R54") (pin "2") (pinfunction "2_2") (pintype "passive"))
      (node (ref "R55") (pin "1") (pinfunction "1_1") (pintype "passive"))
      (node (ref "R56") (pin "1") (pinfunction "1_1") (pintype "passive"))
      (node (ref "R57") (pin "1") (pinfunction "1_1") (pintype "passive"))
      (node (ref "R58") (pin "1") (pinfunction "1_1") (pintype "passive"))
      (node (ref "R59") (pin "1") (pinfunction "1_1") (pintype "passive"))
      (node (ref "REG1") (pin "4") (pinfunction "GND_4") (pintype "power_in"))
      (node (ref "S1") (pin "3") (pinfunction "3_3") (pintype "bidirectional"))
      (node (ref "S1") (pin "4") (pinfunction "4_4") (pintype "bidirectional"))
      (node (ref "U1") (pin "12") (pinfunction "VSSA_12") (pintype "power_in"))
      (node (ref "U1") (pin "18") (pinfunction "VSS_2_18") (pintype "power_in"))
      (node (ref "U1") (pin "3") (pinfunction "PC14-OSC32_IN_3") (pintype "bidirectional"))
      (node (ref "U1") (pin "31") (pinfunction "VSS_3_31") (pintype "power_in"))
      (node (ref "U1") (pin "4") (pinfunction "PC15-OSC32_OUT_4") (pintype "bidirectional"))
      (node (ref "U1") (pin "47") (pinfunction "VSS_4_47") (pintype "power_in"))
      (node (ref "U1") (pin "63") (pinfunction "VSS_63") (pintype "power_in"))
      (node (ref "U2") (pin "1") (pinfunction "~{G1}_1") (pintype "input"))
      (node (ref "U2") (pin "10") (pinfunction "GND_10") (pintype "power_in"))
      (node (ref "U2") (pin "19") (pinfunction "~{G2}_19") (pintype "input"))
      (node (ref "U3") (pin "1") (pinfunction "~{G1}_1") (pintype "input"))
      (node (ref "U3") (pin "10") (pinfunction "GND_10") (pintype "power_in"))
      (node (ref "U3") (pin "19") (pinfunction "~{G2}_19") (pintype "input"))
      (node (ref "U4") (pin "1") (pinfunction "~{G1}_1") (pintype "input"))
      (node (ref "U4") (pin "10") (pinfunction "GND_10") (pintype "power_in"))
      (node (ref "U4") (pin "19") (pinfunction "~{G2}_19") (pintype "input"))
      (node (ref "U5") (pin "1") (pinfunction "~{G1}_1") (pintype "input"))
      (node (ref "U5") (pin "10") (pinfunction "GND_10") (pintype "power_in"))
      (node (ref "U5") (pin "19") (pinfunction "~{G2}_19") (pintype "input"))
      (node (ref "Y1") (pin "2") (pinfunction "GND_1_2") (pintype "bidirectional"))
      (node (ref "Y1") (pin "4") (pinfunction "GND_2_4") (pintype "bidirectional"))
    )
    (net (code "90") (name "Net-(LED1-PadC)") (class "Default")
      (node (ref "LED1") (pin "C") (pinfunction "C_C") (pintype "passive"))
      (node (ref "R22") (pin "2") (pinfunction "2_2") (pintype "passive"))
    )
    (net (code "91") (name "Net-(LED2-PadC)") (class "Default")
      (node (ref "LED2") (pin "C") (pinfunction "C_C") (pintype "passive"))
      (node (ref "R23") (pin "2") (pinfunction "2_2") (pintype "passive"))
    )
    (net (code "92") (name "Net-(LED3-PadC)") (class "Default")
      (node (ref "LED3") (pin "C") (pinfunction "C_C") (pintype "passive"))
      (node (ref "R24") (pin "2") (pinfunction "2_2") (pintype "passive"))
    )
    (net (code "93") (name "Net-(U1A-BOOT0)") (class "Default")
      (node (ref "R19") (pin "2") (pinfunction "2_2") (pintype "passive"))
      (node (ref "U1") (pin "60") (pinfunction "BOOT0_60") (pintype "input"))
    )
    (net (code "94") (name "Net-(U1A-PC0)") (class "Default")
      (node (ref "R22") (pin "1") (pinfunction "1_1") (pintype "passive"))
      (node (ref "U1") (pin "8") (pinfunction "PC0_8") (pintype "bidirectional"))
    )
    (net (code "95") (name "Net-(U1A-PC1)") (class "Default")
      (node (ref "R23") (pin "1") (pinfunction "1_1") (pintype "passive"))
      (node (ref "U1") (pin "9") (pinfunction "PC1_9") (pintype "bidirectional"))
    )
    (net (code "96") (name "Net-(U1A-PC2)") (class "Default")
      (node (ref "R24") (pin "1") (pinfunction "1_1") (pintype "passive"))
      (node (ref "U1") (pin "10") (pinfunction "PC2_10") (pintype "bidirectional"))
    )
    (net (code "97") (name "VCC") (class "Default")
      (node (ref "C11") (pin "1") (pinfunction "+_1") (pintype "bidirectional"))
      (node (ref "C12") (pin "1") (pinfunction "1_1") (pintype "passive"))
      (node (ref "C13") (pin "1") (pinfunction "1_1") (pintype "passive"))
      (node (ref "C14") (pin "2") (pinfunction "2_2") (pintype "passive"))
      (node (ref "C15") (pin "2") (pinfunction "2_2") (pintype "passive"))
      (node (ref "C17") (pin "1") (pinfunction "1_1") (pintype "passive"))
      (node (ref "C18") (pin "1") (pinfunction "1_1") (pintype "passive"))
      (node (ref "C7") (pin "1") (pinfunction "1_1") (pintype "passive"))
      (node (ref "CR2") (pin "5") (pinfunction "VBUS_5") (pintype "power_in"))
      (node (ref "IC1") (pin "24") (pinfunction "VDD(P)_24") (pintype "bidirectional"))
      (node (ref "IC2") (pin "21") (pinfunction "ADDR_21") (pintype "bidirectional"))
      (node (ref "IC2") (pin "24") (pinfunction "VDD(P)_24") (pintype "bidirectional"))
      (node (ref "J1") (pin "1") (pinfunction "1_1") (pintype "bidirectional"))
      (node (ref "JP1") (pin "10") (pinfunction "10_10") (pintype "passive"))
      (node (ref "JP1") (pin "9") (pinfunction "9_9") (pintype "passive"))
      (node (ref "JP4") (pin "1") (pinfunction "1_1") (pintype "passive"))
      (node (ref "JP4") (pin "2") (pinfunction "2_2") (pintype "passive"))
      (node (ref "JP4") (pin "3") (pinfunction "3_3") (pintype "passive"))
      (node (ref "REG1") (pin "1") (pinfunction "IN_1") (pintype "power_in"))
      (node (ref "U2") (pin "20") (pinfunction "VCC_20") (pintype "power_in"))
      (node (ref "U3") (pin "20") (pinfunction "VCC_20") (pintype "power_in"))
      (node (ref "U4") (pin "20") (pinfunction "VCC_20") (pintype "power_in"))
      (node (ref "U5") (pin "20") (pinfunction "VCC_20") (pintype "power_in"))
    )
    (net (code "98") (name "unconnected-(JP1-Pad3)") (class "Default")
      (node (ref "JP1") (pin "3") (pinfunction "3_3") (pintype "passive"))
    )
    (net (code "99") (name "unconnected-(U1A-PA0-Pad14)") (class "Default")
      (node (ref "U1") (pin "14") (pinfunction "PA0_14") (pintype "bidirectional"))
    )
    (net (code "100") (name "unconnected-(U1A-PA1-Pad15)") (class "Default")
      (node (ref "U1") (pin "15") (pinfunction "PA1_15") (pintype "bidirectional"))
    )
    (net (code "101") (name "unconnected-(U1A-PA5-Pad21)") (class "Default")
      (node (ref "U1") (pin "21") (pinfunction "PA5_21") (pintype "bidirectional"))
    )
    (net (code "102") (name "unconnected-(U1A-PA6-Pad22)") (class "Default")
      (node (ref "U1") (pin "22") (pinfunction "PA6_22") (pintype "bidirectional"))
    )
    (net (code "103") (name "unconnected-(U1A-PA7-Pad23)") (class "Default")
      (node (ref "U1") (pin "23") (pinfunction "PA7_23") (pintype "bidirectional"))
    )
    (net (code "104") (name "unconnected-(U1A-PA8-Pad41)") (class "Default")
      (node (ref "U1") (pin "41") (pinfunction "PA8_41") (pintype "bidirectional"))
    )
    (net (code "105") (name "unconnected-(U1A-PA9-Pad42)") (class "Default")
      (node (ref "U1") (pin "42") (pinfunction "PA9_42") (pintype "bidirectional"))
    )
    (net (code "106") (name "unconnected-(U1A-PA10-Pad43)") (class "Default")
      (node (ref "U1") (pin "43") (pinfunction "PA10_43") (pintype "bidirectional"))
    )
    (net (code "107") (name "unconnected-(U1A-PA15-Pad50)") (class "Default")
      (node (ref "U1") (pin "50") (pinfunction "PA15_50") (pintype "bidirectional"))
    )
    (net (code "108") (name "unconnected-(U1A-PB0-Pad26)") (class "Default")
      (node (ref "U1") (pin "26") (pinfunction "PB0_26") (pintype "bidirectional"))
    )
    (net (code "109") (name "unconnected-(U1A-PB1-Pad27)") (class "Default")
      (node (ref "U1") (pin "27") (pinfunction "PB1_27") (pintype "bidirectional"))
    )
    (net (code "110") (name "unconnected-(U1A-PB2-Pad28)") (class "Default")
      (node (ref "U1") (pin "28") (pinfunction "PB2_28") (pintype "bidirectional"))
    )
    (net (code "111") (name "unconnected-(U1A-PB3-Pad55)") (class "Default")
      (node (ref "U1") (pin "55") (pinfunction "PB3_55") (pintype "bidirectional"))
    )
    (net (code "112") (name "unconnected-(U1A-PB4-Pad56)") (class "Default")
      (node (ref "U1") (pin "56") (pinfunction "PB4_56") (pintype "bidirectional"))
    )
    (net (code "113") (name "unconnected-(U1A-PB5-Pad57)") (class "Default")
      (node (ref "U1") (pin "57") (pinfunction "PB5_57") (pintype "bidirectional"))
    )
    (net (code "114") (name "unconnected-(U1A-PB8-Pad61)") (class "Default")
      (node (ref "U1") (pin "61") (pinfunction "PB8_61") (pintype "bidirectional"))
    )
    (net (code "115") (name "unconnected-(U1A-PB9-Pad62)") (class "Default")
      (node (ref "U1") (pin "62") (pinfunction "PB9_62") (pintype "bidirectional"))
    )
    (net (code "116") (name "unconnected-(U1A-PB10-Pad29)") (class "Default")
      (node (ref "U1") (pin "29") (pinfunction "PB10_29") (pintype "bidirectional"))
    )
    (net (code "117") (name "unconnected-(U1A-PB11-Pad30)") (class "Default")
      (node (ref "U1") (pin "30") (pinfunction "PB11_30") (pintype "bidirectional"))
    )
    (net (code "118") (name "unconnected-(U1A-PC4-Pad24)") (class "Default")
      (node (ref "U1") (pin "24") (pinfunction "PC4_24") (pintype "bidirectional"))
    )
    (net (code "119") (name "unconnected-(U1A-PC6-Pad37)") (class "Default")
      (node (ref "U1") (pin "37") (pinfunction "PC6_37") (pintype "bidirectional"))
    )
    (net (code "120") (name "unconnected-(U1A-PC7-Pad38)") (class "Default")
      (node (ref "U1") (pin "38") (pinfunction "PC7_38") (pintype "bidirectional"))
    )
    (net (code "121") (name "unconnected-(U1A-PC8-Pad39)") (class "Default")
      (node (ref "U1") (pin "39") (pinfunction "PC8_39") (pintype "bidirectional"))
    )
    (net (code "122") (name "unconnected-(U1A-PC9-Pad40)") (class "Default")
      (node (ref "U1") (pin "40") (pinfunction "PC9_40") (pintype "bidirectional"))
    )
    (net (code "123") (name "unconnected-(U1A-PC10-Pad51)") (class "Default")
      (node (ref "U1") (pin "51") (pinfunction "PC10_51") (pintype "bidirectional"))
    )
    (net (code "124") (name "unconnected-(U1A-PC13-Pad2)") (class "Default")
      (node (ref "U1") (pin "2") (pinfunction "PC13_2") (pintype "bidirectional"))
    )
    (net (code "125") (name "unconnected-(U1A-PD2-Pad54)") (class "Default")
      (node (ref "U1") (pin "54") (pinfunction "PD2_54") (pintype "bidirectional"))
    )
  )
)
